# CON_FFC40_LCDTFT.net
KiCad netlist of a schematic drawn in Altium Designer
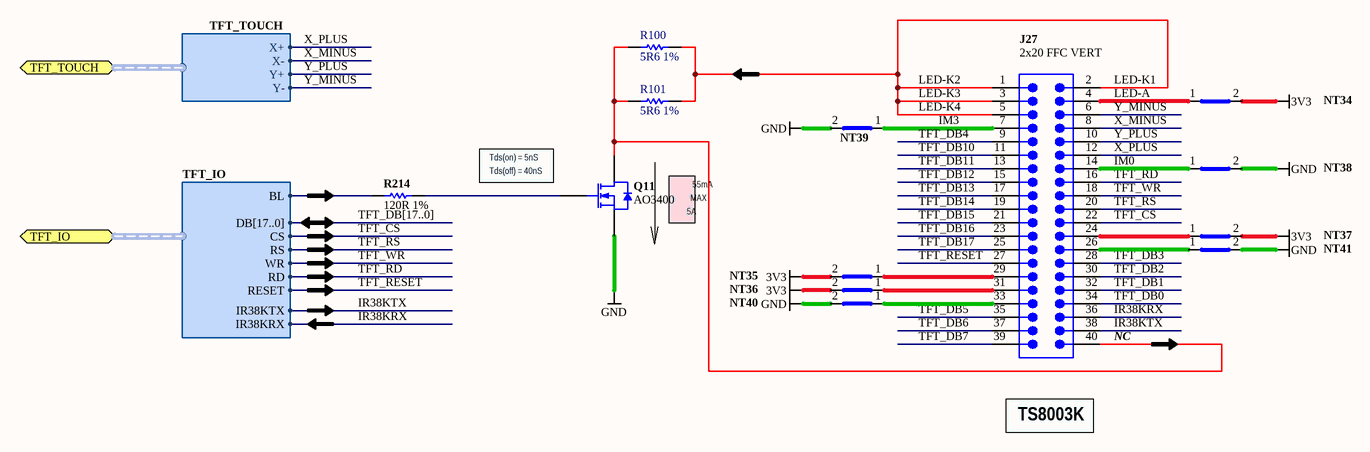
[diagram p0: CON_FFC40_LCDTFT.SCHDOC]

(export (version "E")
  (design (tool "Eeschema 10.0.6"))
  (components
    (comp (ref "J27")
      (value "2x20 FFC VERT")
      (footprint "FPC-xxS1VN3R")
      (description "Header FFC, 2x20 pin Vertical, 0.5mm")
      (libsource (lib "AltiumDesignLibrary") (part "CON-FFC-2x20-VERT"))
    )
    (comp (ref "NT34")
      (value "Net Tie SMT2")
      (footprint "NETTIE-SMT2-8X8")
      (description "Net-Tie, Surface Mount, 2 x 1.6mm x 0.8mm SMT Pads - For 0.8mm Track")
      (libsource (lib "AltiumDesignLibrary") (part "NETTIE-SMT2"))
    )
    (comp (ref "NT35")
      (value "Net Tie SMT2")
      (footprint "NETTIE-SMT2-8X8")
      (description "Net-Tie, Surface Mount, 2 x 1.6mm x 0.8mm SMT Pads - For 0.8mm Track")
      (libsource (lib "AltiumDesignLibrary") (part "NETTIE-SMT2"))
    )
    (comp (ref "NT36")
      (value "Net Tie SMT2")
      (footprint "NETTIE-SMT2-8X8")
      (description "Net-Tie, Surface Mount, 2 x 1.6mm x 0.8mm SMT Pads - For 0.8mm Track")
      (libsource (lib "AltiumDesignLibrary") (part "NETTIE-SMT2"))
    )
    (comp (ref "NT37")
      (value "Net Tie SMT2")
      (footprint "NETTIE-SMT2-8X8")
      (description "Net-Tie, Surface Mount, 2 x 1.6mm x 0.8mm SMT Pads - For 0.8mm Track")
      (libsource (lib "AltiumDesignLibrary") (part "NETTIE-SMT2"))
    )
    (comp (ref "NT38")
      (value "Net Tie SMT2")
      (footprint "NETTIE-SMT2-8X8")
      (description "Net-Tie, Surface Mount, 2 x 1.6mm x 0.8mm SMT Pads - For 0.8mm Track")
      (libsource (lib "AltiumDesignLibrary") (part "NETTIE-SMT2"))
    )
    (comp (ref "NT39")
      (value "Net Tie SMT2")
      (footprint "NETTIE-SMT2-8X8")
      (description "Net-Tie, Surface Mount, 2 x 1.6mm x 0.8mm SMT Pads - For 0.8mm Track")
      (libsource (lib "AltiumDesignLibrary") (part "NETTIE-SMT2"))
    )
    (comp (ref "NT40")
      (value "Net Tie SMT2")
      (footprint "NETTIE-SMT2-8X8")
      (description "Net-Tie, Surface Mount, 2 x 1.6mm x 0.8mm SMT Pads - For 0.8mm Track")
      (libsource (lib "AltiumDesignLibrary") (part "NETTIE-SMT2"))
    )
    (comp (ref "NT41")
      (value "Net Tie SMT2")
      (footprint "NETTIE-SMT2-8X8")
      (description "Net-Tie, Surface Mount, 2 x 1.6mm x 0.8mm SMT Pads - For 0.8mm Track")
      (libsource (lib "AltiumDesignLibrary") (part "NETTIE-SMT2"))
    )
    (comp (ref "Q11")
      (value "AO3400")
      (footprint "SOT95P230-3D")
      (description "N-channel Enhancement Mode Field-effect Transistor;  5.8A/30V")
      (libsource (lib "AltiumDesignLibrary") (part "N-Channel-FET"))
    )
    (comp (ref "R100")
      (value "5R6 1%")
      (footprint "RESC1005-STAR")
      (description "Resistor, 5R6 1% 0402 (1005)")
      (fields (field (name "TOLERANCE") "1%"))
      (libsource (lib "AltiumDesignLibrary") (part "RES"))
    )
    (comp (ref "R101")
      (value "5R6 1%")
      (footprint "RESC1005-STAR")
      (description "Resistor, 5R6 1% 0402 (1005)")
      (fields (field (name "TOLERANCE") "1%"))
      (libsource (lib "AltiumDesignLibrary") (part "RES"))
    )
    (comp (ref "R214")
      (value "120R 1%")
      (footprint "RESC1005-STAR")
      (description "Resistor, 120R 1% 0402 (1005)")
      (fields (field (name "TOLERANCE") "1 %"))
      (libsource (lib "AltiumDesignLibrary") (part "RES"))
    )
  )
  (nets
    (net (code "3") (name "/BL") (class "Default")
      (node (ref "R214") (pin "2") (pinfunction "2_2") (pintype "passive"))
    )
    (net (code "4") (name "/IR38KRX") (class "Default")
      (node (ref "J27") (pin "36") (pinfunction "36_36") (pintype "passive"))
    )
    (net (code "5") (name "/IR38KTX") (class "Default")
      (node (ref "J27") (pin "38") (pinfunction "38_38") (pintype "passive"))
    )
    (net (code "6") (name "/TFT_CS") (class "Default")
      (node (ref "J27") (pin "22") (pinfunction "22_22") (pintype "passive"))
    )
    (net (code "7") (name "/TFT_DB0") (class "Default")
      (node (ref "J27") (pin "34") (pinfunction "34_34") (pintype "passive"))
    )
    (net (code "8") (name "/TFT_DB1") (class "Default")
      (node (ref "J27") (pin "32") (pinfunction "32_32") (pintype "passive"))
    )
    (net (code "9") (name "/TFT_DB2") (class "Default")
      (node (ref "J27") (pin "30") (pinfunction "30_30") (pintype "passive"))
    )
    (net (code "10") (name "/TFT_DB3") (class "Default")
      (node (ref "J27") (pin "28") (pinfunction "28_28") (pintype "passive"))
    )
    (net (code "11") (name "/TFT_DB4") (class "Default")
      (node (ref "J27") (pin "9") (pinfunction "9_9") (pintype "passive"))
    )
    (net (code "12") (name "/TFT_DB5") (class "Default")
      (node (ref "J27") (pin "35") (pinfunction "35_35") (pintype "passive"))
    )
    (net (code "13") (name "/TFT_DB6") (class "Default")
      (node (ref "J27") (pin "37") (pinfunction "37_37") (pintype "passive"))
    )
    (net (code "14") (name "/TFT_DB7") (class "Default")
      (node (ref "J27") (pin "39") (pinfunction "39_39") (pintype "passive"))
    )
    (net (code "15") (name "/TFT_DB10") (class "Default")
      (node (ref "J27") (pin "11") (pinfunction "11_11") (pintype "passive"))
    )
    (net (code "16") (name "/TFT_DB11") (class "Default")
      (node (ref "J27") (pin "13") (pinfunction "13_13") (pintype "passive"))
    )
    (net (code "17") (name "/TFT_DB12") (class "Default")
      (node (ref "J27") (pin "15") (pinfunction "15_15") (pintype "passive"))
    )
    (net (code "18") (name "/TFT_DB13") (class "Default")
      (node (ref "J27") (pin "17") (pinfunction "17_17") (pintype "passive"))
    )
    (net (code "19") (name "/TFT_DB14") (class "Default")
      (node (ref "J27") (pin "19") (pinfunction "19_19") (pintype "passive"))
    )
    (net (code "20") (name "/TFT_DB15") (class "Default")
      (node (ref "J27") (pin "21") (pinfunction "21_21") (pintype "passive"))
    )
    (net (code "21") (name "/TFT_DB16") (class "Default")
      (node (ref "J27") (pin "23") (pinfunction "23_23") (pintype "passive"))
    )
    (net (code "22") (name "/TFT_DB17") (class "Default")
      (node (ref "J27") (pin "25") (pinfunction "25_25") (pintype "passive"))
    )
    (net (code "24") (name "/TFT_RD") (class "Default")
      (node (ref "J27") (pin "16") (pinfunction "16_16") (pintype "passive"))
    )
    (net (code "25") (name "/TFT_RESET") (class "Default")
      (node (ref "J27") (pin "27") (pinfunction "27_27") (pintype "passive"))
    )
    (net (code "26") (name "/TFT_RS") (class "Default")
      (node (ref "J27") (pin "20") (pinfunction "20_20") (pintype "passive"))
    )
    (net (code "27") (name "/TFT_WR") (class "Default")
      (node (ref "J27") (pin "18") (pinfunction "18_18") (pintype "passive"))
    )
    (net (code "28") (name "/X_MINUS") (class "Default")
      (node (ref "J27") (pin "8") (pinfunction "8_8") (pintype "passive"))
    )
    (net (code "29") (name "/X_PLUS") (class "Default")
      (node (ref "J27") (pin "12") (pinfunction "12_12") (pintype "passive"))
    )
    (net (code "30") (name "/Y_MINUS") (class "Default")
      (node (ref "J27") (pin "6") (pinfunction "6_6") (pintype "passive"))
    )
    (net (code "31") (name "/Y_PLUS") (class "Default")
      (node (ref "J27") (pin "10") (pinfunction "10_10") (pintype "passive"))
    )
    (net (code "33") (name "3V3") (class "Default")
      (node (ref "NT34") (pin "2") (pinfunction "Net2_2") (pintype "passive"))
      (node (ref "NT35") (pin "2") (pinfunction "Net2_2") (pintype "passive"))
      (node (ref "NT36") (pin "2") (pinfunction "Net2_2") (pintype "passive"))
      (node (ref "NT37") (pin "2") (pinfunction "Net2_2") (pintype "passive"))
    )
    (net (code "34") (name "GND") (class "Default")
      (node (ref "NT38") (pin "2") (pinfunction "Net2_2") (pintype "passive"))
      (node (ref "NT39") (pin "2") (pinfunction "Net2_2") (pintype "passive"))
      (node (ref "NT40") (pin "2") (pinfunction "Net2_2") (pintype "passive"))
      (node (ref "NT41") (pin "2") (pinfunction "Net2_2") (pintype "passive"))
      (node (ref "Q11") (pin "3") (pinfunction "S_3") (pintype "passive"))
    )
    (net (code "35") (name "Net-(J27-Pad1)") (class "Default")
      (node (ref "J27") (pin "1") (pinfunction "1_1") (pintype "passive"))
      (node (ref "J27") (pin "2") (pinfunction "2_2") (pintype "passive"))
      (node (ref "J27") (pin "3") (pinfunction "3_3") (pintype "passive"))
      (node (ref "J27") (pin "5") (pinfunction "5_5") (pintype "passive"))
      (node (ref "R100") (pin "1") (pinfunction "1_1") (pintype "passive"))
      (node (ref "R101") (pin "1") (pinfunction "1_1") (pintype "passive"))
    )
    (net (code "36") (name "Net-(NT34-Net1)") (class "Default")
      (node (ref "J27") (pin "4") (pinfunction "4_4") (pintype "passive"))
      (node (ref "NT34") (pin "1") (pinfunction "Net1_1") (pintype "passive"))
    )
    (net (code "37") (name "Net-(NT35-Net1)") (class "Default")
      (node (ref "J27") (pin "29") (pinfunction "29_29") (pintype "passive"))
      (node (ref "NT35") (pin "1") (pinfunction "Net1_1") (pintype "passive"))
    )
    (net (code "38") (name "Net-(NT36-Net1)") (class "Default")
      (node (ref "J27") (pin "31") (pinfunction "31_31") (pintype "passive"))
      (node (ref "NT36") (pin "1") (pinfunction "Net1_1") (pintype "passive"))
    )
    (net (code "39") (name "Net-(NT37-Net1)") (class "Default")
      (node (ref "J27") (pin "24") (pinfunction "24_24") (pintype "passive"))
      (node (ref "NT37") (pin "1") (pinfunction "Net1_1") (pintype "passive"))
    )
    (net (code "40") (name "Net-(NT38-Net1)") (class "Default")
      (node (ref "J27") (pin "14") (pinfunction "14_14") (pintype "passive"))
      (node (ref "NT38") (pin "1") (pinfunction "Net1_1") (pintype "passive"))
    )
    (net (code "41") (name "Net-(NT39-Net1)") (class "Default")
      (node (ref "J27") (pin "7") (pinfunction "7_7") (pintype "passive"))
      (node (ref "NT39") (pin "1") (pinfunction "Net1_1") (pintype "passive"))
    )
    (net (code "42") (name "Net-(NT40-Net1)") (class "Default")
      (node (ref "J27") (pin "33") (pinfunction "33_33") (pintype "passive"))
      (node (ref "NT40") (pin "1") (pinfunction "Net1_1") (pintype "passive"))
    )
    (net (code "43") (name "Net-(NT41-Net1)") (class "Default")
      (node (ref "J27") (pin "26") (pinfunction "26_26") (pintype "passive"))
      (node (ref "NT41") (pin "1") (pinfunction "Net1_1") (pintype "passive"))
    )
    (net (code "44") (name "Net-(Q11-D)") (class "Default")
      (node (ref "J27") (pin "40") (pinfunction "40_40") (pintype "passive"))
      (node (ref "Q11") (pin "2") (pinfunction "D_2") (pintype "passive"))
      (node (ref "R100") (pin "2") (pinfunction "2_2") (pintype "passive"))
      (node (ref "R101") (pin "2") (pinfunction "2_2") (pintype "passive"))
    )
    (net (code "45") (name "Net-(Q11-G)") (class "Default")
      (node (ref "Q11") (pin "1") (pinfunction "G_1") (pintype "passive"))
      (node (ref "R214") (pin "1") (pinfunction "1_1") (pintype "passive"))
    )
  )
)
